# 08.net
KiCad netlist of a schematic drawn in Altium Designer
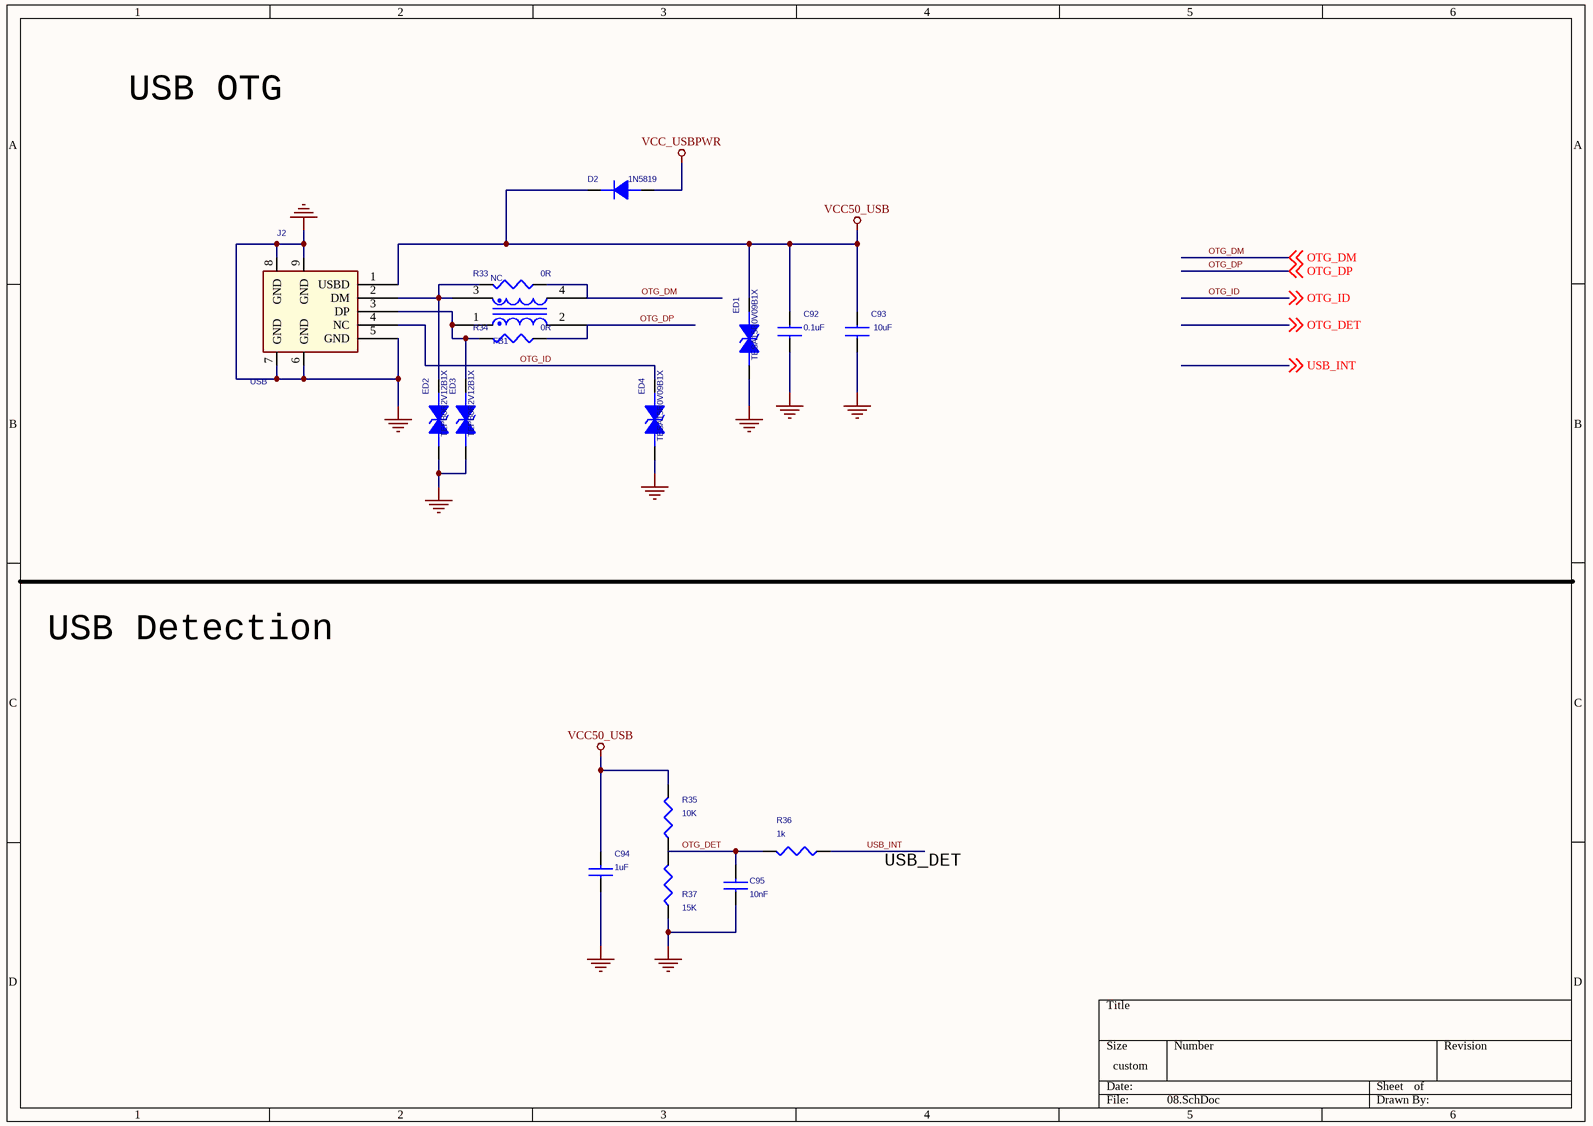
[diagram p0: 08.SchDoc]

(export (version "E")
  (design (tool "Eeschema 10.0.6"))
  (components
    (comp (ref "C92")
      (value "0.1uF")
      (footprint "C0603")
      (description "贴片电容")
      (libsource (lib "*") (part "CAP NP_Dup3"))
    )
    (comp (ref "C93") (value "10uF") (footprint "C0603") (libsource (lib "*") (part "CAP NP_Dup3")))
    (comp (ref "C94")
      (value "1uF")
      (footprint "C0402")
      (description "RoHS CHIP CAP 1uF +10/-10% X5R")
      (libsource (lib "*") (part "CAP NP_Dup2"))
    )
    (comp (ref "C95")
      (value "10nF")
      (footprint "C0402")
      (description "RoHS CHIP CAP 10nF +10/-10% X7R")
      (libsource (lib "*") (part "CAP NP_Dup2"))
    )
    (comp (ref "D2")
      (value "1N5819")
      (footprint "SOD123")
      (description "Diode,Schottky,1N5819HW,40V,500mA,450mV")
      (libsource (lib "*") (part "DIODE"))
    )
    (comp (ref "ED1")
      (value "TESA15R0V09B1X")
      (footprint "E0402N")
      (description "ESD Component,5V,30P,SMD,0402")
      (libsource (lib "*") (part "TVS"))
    )
    (comp (ref "ED2")
      (value "TEPB0R2V12B1X")
      (footprint "E0402N")
      (description "ESD Component,5V,30P,SMD,0402")
      (libsource (lib "*") (part "TVS"))
    )
    (comp (ref "ED3")
      (value "TEPB0R2V12B1X")
      (footprint "E0402N")
      (description "ESD Component,5V,30P,SMD,0402")
      (libsource (lib "*") (part "TVS"))
    )
    (comp (ref "ED4")
      (value "TESA15R0V09B1X")
      (footprint "E0402N")
      (description "ESD Component,5V,30P,SMD,0402")
      (libsource (lib "*") (part "TVS"))
    )
    (comp (ref "FB1")
      (value "NC")
      (footprint "LL-4")
      (description "Chip common mode choke coil,90 ohm@100MHz,0.35 ohm/DCR,50V,330mA,-40°C~+ 85°C")
      (libsource (lib "*") (part "L_CHOKE CM14"))
    )
    (comp (ref "J2") (value "USB") (footprint "MICRO_USB_DIP") (libsource (lib "*") (part "MINI USB_0")))
    (comp (ref "R33")
      (value "0R")
      (footprint "r0402")
      (description "RES,thick film,10KOhm,+/-5%,1/16W,SMD0402")
      (libsource (lib "*") (part "RESISTOR_0_Dup3"))
    )
    (comp (ref "R34")
      (value "0R")
      (footprint "r0402")
      (description "RES,thick film,10KOhm,+/-5%,1/16W,SMD0402")
      (libsource (lib "*") (part "RESISTOR_0_Dup3"))
    )
    (comp (ref "R35")
      (value "10K")
      (footprint "R0402")
      (description "ROHS CHIP RES 10K 1/16W 5%")
      (libsource (lib "*") (part "RESISTOR_Dup1"))
    )
    (comp (ref "R36")
      (value "1k")
      (footprint "R0402")
      (description "ROHS CHIP RES 10K 1/16W 5%")
      (libsource (lib "*") (part "RESISTOR_Dup1"))
    )
    (comp (ref "R37")
      (value "15K")
      (footprint "R0402")
      (description "ROHS CHIP RES 15K 1/16W 5%")
      (libsource (lib "*") (part "RESISTOR_Dup1"))
    )
  )
  (nets
    (net (code "1") (name "GND") (class "Default")
      (node (ref "C92") (pin "1") (pinfunction "1_1") (pintype "passive"))
      (node (ref "C93") (pin "2") (pinfunction "2_2") (pintype "passive"))
      (node (ref "C94") (pin "1") (pinfunction "1_1") (pintype "passive"))
      (node (ref "C95") (pin "1") (pinfunction "1_1") (pintype "passive"))
      (node (ref "ED1") (pin "2") (pinfunction "2_2") (pintype "passive"))
      (node (ref "ED2") (pin "2") (pinfunction "2_2") (pintype "passive"))
      (node (ref "ED3") (pin "2") (pinfunction "2_2") (pintype "passive"))
      (node (ref "ED4") (pin "2") (pinfunction "2_2") (pintype "passive"))
      (node (ref "J2") (pin "5") (pinfunction "GND_5") (pintype "power_in"))
      (node (ref "J2") (pin "6") (pinfunction "GND_6") (pintype "power_in"))
      (node (ref "J2") (pin "7") (pinfunction "GND_7") (pintype "power_in"))
      (node (ref "J2") (pin "8") (pinfunction "GND_8") (pintype "power_in"))
      (node (ref "J2") (pin "9") (pinfunction "GND_9") (pintype "power_in"))
      (node (ref "R37") (pin "1") (pinfunction "1_1") (pintype "passive"))
    )
    (net (code "2") (name "Net-(J2-DM)") (class "Default")
      (node (ref "ED2") (pin "1") (pinfunction "1_1") (pintype "passive"))
      (node (ref "FB1") (pin "3") (pinfunction "3_3") (pintype "passive"))
      (node (ref "J2") (pin "2") (pinfunction "DM_2") (pintype "passive"))
      (node (ref "R33") (pin "2") (pinfunction "2_2") (pintype "passive"))
    )
    (net (code "3") (name "Net-(J2-DP)") (class "Default")
      (node (ref "ED3") (pin "1") (pinfunction "1_1") (pintype "passive"))
      (node (ref "FB1") (pin "1") (pinfunction "1_1") (pintype "passive"))
      (node (ref "J2") (pin "3") (pinfunction "DP_3") (pintype "passive"))
      (node (ref "R34") (pin "2") (pinfunction "2_2") (pintype "passive"))
    )
    (net (code "4") (name "OTG_DET") (class "Default")
      (node (ref "C95") (pin "2") (pinfunction "2_2") (pintype "passive"))
      (node (ref "R35") (pin "1") (pinfunction "1_1") (pintype "passive"))
      (node (ref "R36") (pin "2") (pinfunction "2_2") (pintype "passive"))
      (node (ref "R37") (pin "2") (pinfunction "2_2") (pintype "passive"))
    )
    (net (code "5") (name "OTG_DM") (class "Default")
      (node (ref "FB1") (pin "4") (pinfunction "4_4") (pintype "passive"))
      (node (ref "R33") (pin "1") (pinfunction "1_1") (pintype "passive"))
    )
    (net (code "6") (name "OTG_DP") (class "Default")
      (node (ref "FB1") (pin "2") (pinfunction "2_2") (pintype "passive"))
      (node (ref "R34") (pin "1") (pinfunction "1_1") (pintype "passive"))
    )
    (net (code "7") (name "OTG_ID") (class "Default")
      (node (ref "ED4") (pin "1") (pinfunction "1_1") (pintype "passive"))
      (node (ref "J2") (pin "4") (pinfunction "NC_4") (pintype "passive"))
    )
    (net (code "8") (name "USB_INT") (class "Default")
      (node (ref "R36") (pin "1") (pinfunction "1_1") (pintype "passive"))
    )
    (net (code "9") (name "VCC50_USB") (class "Default")
      (node (ref "C92") (pin "2") (pinfunction "2_2") (pintype "passive"))
      (node (ref "C93") (pin "1") (pinfunction "1_1") (pintype "passive"))
      (node (ref "C94") (pin "2") (pinfunction "2_2") (pintype "passive"))
      (node (ref "D2") (pin "2") (pinfunction "K_2") (pintype "passive"))
      (node (ref "ED1") (pin "1") (pinfunction "1_1") (pintype "passive"))
      (node (ref "J2") (pin "1") (pinfunction "USBD_1") (pintype "passive"))
      (node (ref "R35") (pin "2") (pinfunction "2_2") (pintype "passive"))
    )
    (net (code "10") (name "VCC_USBPWR") (class "Default")
      (node (ref "D2") (pin "1") (pinfunction "A_1") (pintype "passive"))
    )
  )
)
